# ESP32DevKitCv4_SA8x8_Rearrange.net
KiCad netlist of a schematic drawn in EAGLE
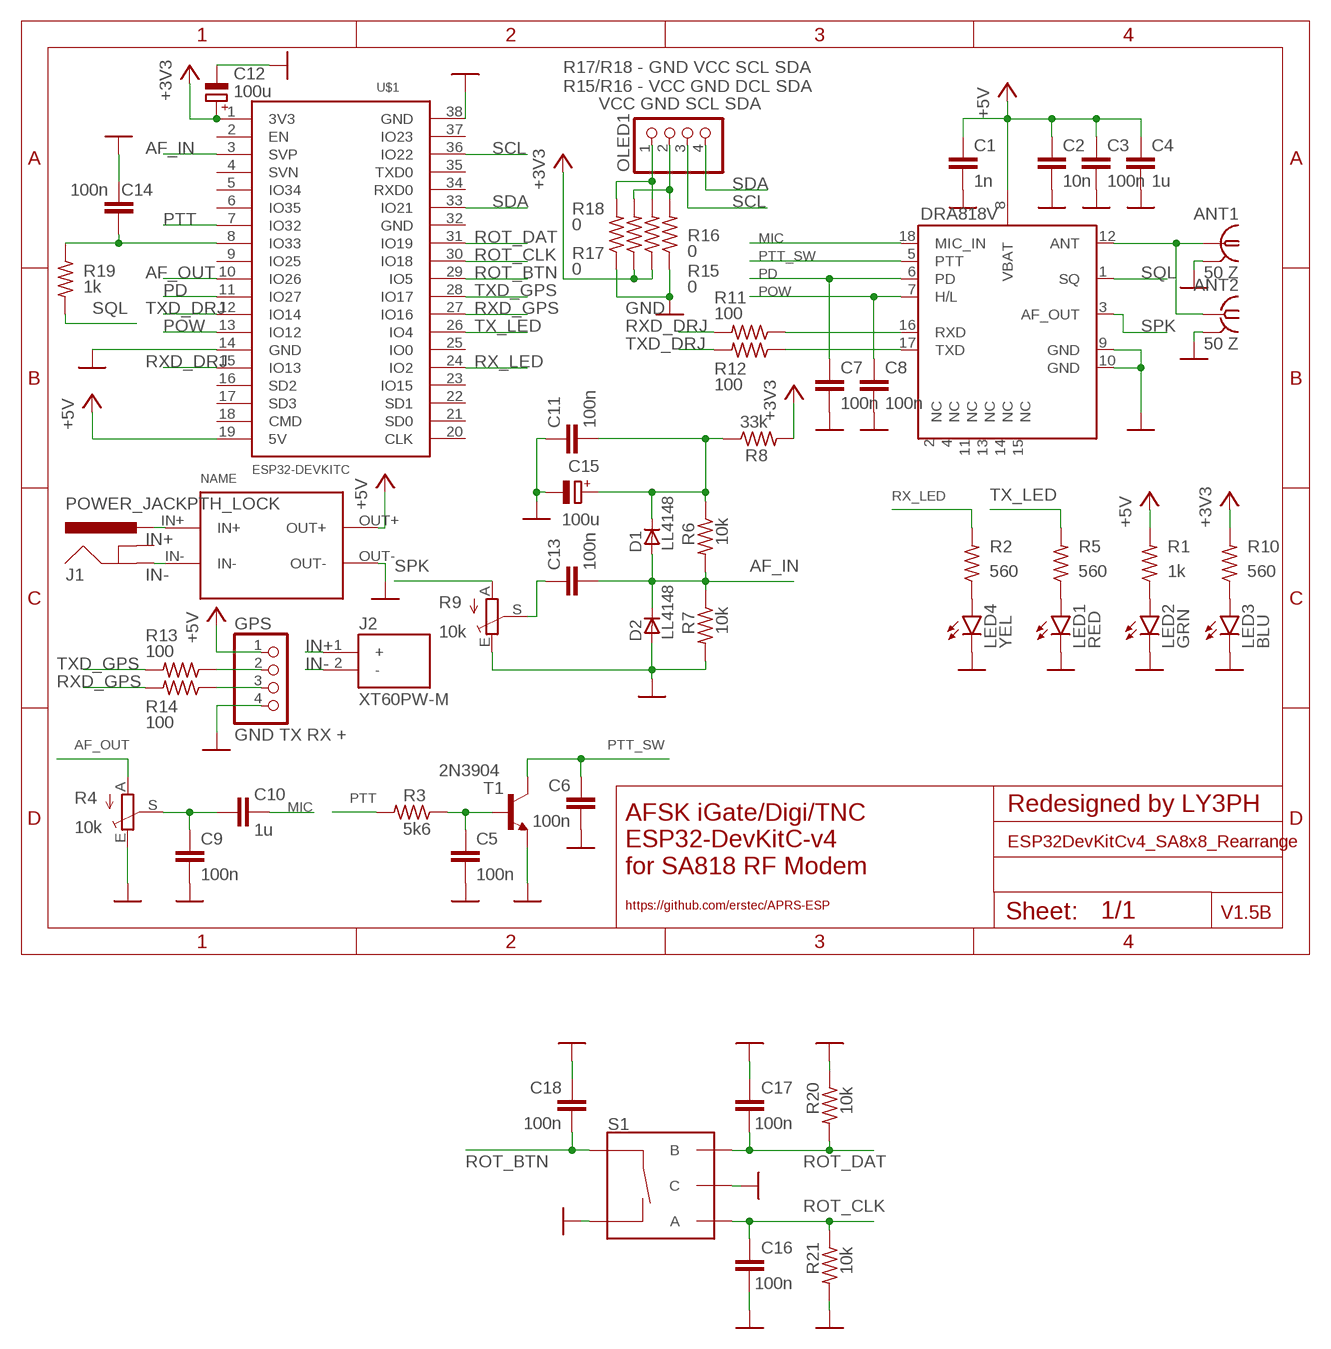
[diagram p0: schematic, sheet 1]

(export (version "E")
  (design (tool "Eeschema 10.0.6"))
  (components
    (comp (ref "ANT1")
      (value "50 Z")
      (footprint "eagle-import:LTI-SASF54GT")
      (libsource (lib "eagle-import") (part "LTI-SASF54GT"))
    )
    (comp (ref "ANT2")
      (value "50 Z")
      (footprint "eagle-import:J502-ND-142-0701-801_806")
      (fields (field (name "MF") "JOHNSON COMPONENTS") (field (name "MPN") "142-0701-801"))
      (libsource (lib "eagle-import") (part "SMA-142-0701-801/806"))
    )
    (comp (ref "C1")
      (value "1n")
      (footprint "eagle-import:C0805")
      (libsource (lib "eagle-import") (part "C-EUC0805"))
    )
    (comp (ref "C2")
      (value "10n")
      (footprint "eagle-import:C0805")
      (libsource (lib "eagle-import") (part "C-EUC0805"))
    )
    (comp (ref "C3")
      (value "100n")
      (footprint "eagle-import:C0805")
      (libsource (lib "eagle-import") (part "C-EUC0805"))
    )
    (comp (ref "C4")
      (value "1u")
      (footprint "eagle-import:C0805")
      (libsource (lib "eagle-import") (part "C-EUC0805"))
    )
    (comp (ref "C5")
      (value "100n")
      (footprint "eagle-import:C0805")
      (libsource (lib "eagle-import") (part "C-EUC0805"))
    )
    (comp (ref "C6")
      (value "100n")
      (footprint "eagle-import:C0805")
      (libsource (lib "eagle-import") (part "C-EUC0805"))
    )
    (comp (ref "C7")
      (value "100n")
      (footprint "eagle-import:C0805")
      (libsource (lib "eagle-import") (part "C-EUC0805"))
    )
    (comp (ref "C8")
      (value "100n")
      (footprint "eagle-import:C0805")
      (libsource (lib "eagle-import") (part "C-EUC0805"))
    )
    (comp (ref "C9")
      (value "100n")
      (footprint "eagle-import:C0805")
      (libsource (lib "eagle-import") (part "C-EUC0805"))
    )
    (comp (ref "C10")
      (value "1u")
      (footprint "eagle-import:C0805")
      (libsource (lib "eagle-import") (part "C-EUC0805"))
    )
    (comp (ref "C11")
      (value "100n")
      (footprint "eagle-import:C0805")
      (libsource (lib "eagle-import") (part "C-EUC0805"))
    )
    (comp (ref "C12")
      (value "100u")
      (footprint "eagle-import:SMC_D")
      (libsource (lib "eagle-import") (part "CPOL-EUSMCD"))
    )
    (comp (ref "C13")
      (value "100n")
      (footprint "eagle-import:C0805")
      (libsource (lib "eagle-import") (part "C-EUC0805"))
    )
    (comp (ref "C14")
      (value "100n")
      (footprint "eagle-import:C0805")
      (libsource (lib "eagle-import") (part "C-EUC0805"))
    )
    (comp (ref "C15")
      (value "100u")
      (footprint "eagle-import:SMC_D")
      (libsource (lib "eagle-import") (part "CPOL-EUSMCD"))
    )
    (comp (ref "C16")
      (value "100n")
      (footprint "eagle-import:C0805")
      (libsource (lib "eagle-import") (part "C-EUC0805"))
    )
    (comp (ref "C17")
      (value "100n")
      (footprint "eagle-import:C0805")
      (libsource (lib "eagle-import") (part "C-EUC0805"))
    )
    (comp (ref "C18")
      (value "100n")
      (footprint "eagle-import:C0805")
      (libsource (lib "eagle-import") (part "C-EUC0805"))
    )
    (comp (ref "D1")
      (value "LL4148")
      (footprint "eagle-import:SOD80_DO213AA_MINIMELF")
      (libsource (lib "eagle-import") (part "LL4148"))
    )
    (comp (ref "D2")
      (value "LL4148")
      (footprint "eagle-import:SOD80_DO213AA_MINIMELF")
      (libsource (lib "eagle-import") (part "LL4148"))
    )
    (comp (ref "DRA818V")
      (value "DRA818A")
      (footprint "eagle-import:DRA818A")
      (libsource (lib "eagle-import") (part "DRA818A"))
    )
    (comp (ref "GPS")
      (value "GND TX RX +")
      (footprint "eagle-import:1X04")
      (libsource (lib "eagle-import") (part "PINHD-1X4"))
    )
    (comp (ref "J1")
      (value "POWER_JACKPTH_LOCK")
      (footprint "eagle-import:POWER_JACK_PTH_LOCK")
      (libsource (lib "eagle-import") (part "POWER_JACKPTH_LOCK"))
    )
    (comp (ref "J2")
      (value "XT60PW-M")
      (footprint "eagle-import:AMASS_XT60PW-M")
      (fields (field (name "MF") "AMASS"))
      (libsource (lib "eagle-import") (part "XT60PW-M"))
    )
    (comp (ref "LED1")
      (value "RED")
      (footprint "eagle-import:CHIP-LED0805")
      (libsource (lib "eagle-import") (part "LEDCHIP-LED0805"))
    )
    (comp (ref "LED2")
      (value "GRN")
      (footprint "eagle-import:CHIP-LED0805")
      (libsource (lib "eagle-import") (part "LEDCHIP-LED0805"))
    )
    (comp (ref "LED3")
      (value "BLU")
      (footprint "eagle-import:CHIP-LED0805")
      (libsource (lib "eagle-import") (part "LEDCHIP-LED0805"))
    )
    (comp (ref "LED4")
      (value "YEL")
      (footprint "eagle-import:CHIP-LED0805")
      (libsource (lib "eagle-import") (part "LEDCHIP-LED0805"))
    )
    (comp (ref "OLED1")
      (value "VCC GND SCL SDA")
      (footprint "eagle-import:1X04")
      (libsource (lib "eagle-import") (part "PINHD-1X4"))
    )
    (comp (ref "R1")
      (value "1k")
      (footprint "eagle-import:R0805")
      (libsource (lib "eagle-import") (part "R-US_R0805"))
    )
    (comp (ref "R2")
      (value "560")
      (footprint "eagle-import:R0805")
      (libsource (lib "eagle-import") (part "R-US_R0805"))
    )
    (comp (ref "R3")
      (value "5k6")
      (footprint "eagle-import:R0805")
      (libsource (lib "eagle-import") (part "R-US_R0805"))
    )
    (comp (ref "R4")
      (value "10k")
      (footprint "eagle-import:CA6H")
      (libsource (lib "eagle-import") (part "TRIM_EU-CA6H"))
    )
    (comp (ref "R5")
      (value "560")
      (footprint "eagle-import:R0805")
      (libsource (lib "eagle-import") (part "R-US_R0805"))
    )
    (comp (ref "R6")
      (value "10k")
      (footprint "eagle-import:R0805")
      (libsource (lib "eagle-import") (part "R-US_R0805"))
    )
    (comp (ref "R7")
      (value "10k")
      (footprint "eagle-import:R0805")
      (libsource (lib "eagle-import") (part "R-US_R0805"))
    )
    (comp (ref "R8")
      (value "33k")
      (footprint "eagle-import:R0805")
      (libsource (lib "eagle-import") (part "R-US_R0805"))
    )
    (comp (ref "R9")
      (value "10k")
      (footprint "eagle-import:CA6H")
      (libsource (lib "eagle-import") (part "TRIM_EU-CA6H"))
    )
    (comp (ref "R10")
      (value "560")
      (footprint "eagle-import:R0805")
      (libsource (lib "eagle-import") (part "R-US_R0805"))
    )
    (comp (ref "R11")
      (value "100")
      (footprint "eagle-import:R0805")
      (libsource (lib "eagle-import") (part "R-US_R0805"))
    )
    (comp (ref "R12")
      (value "100")
      (footprint "eagle-import:R0805")
      (libsource (lib "eagle-import") (part "R-US_R0805"))
    )
    (comp (ref "R13")
      (value "100")
      (footprint "eagle-import:R0805")
      (libsource (lib "eagle-import") (part "R-US_R0805"))
    )
    (comp (ref "R14")
      (value "100")
      (footprint "eagle-import:R0805")
      (libsource (lib "eagle-import") (part "R-US_R0805"))
    )
    (comp (ref "R15")
      (value "0")
      (footprint "eagle-import:R0805")
      (libsource (lib "eagle-import") (part "R-US_R0805"))
    )
    (comp (ref "R16")
      (value "0")
      (footprint "eagle-import:R0805")
      (libsource (lib "eagle-import") (part "R-US_R0805"))
    )
    (comp (ref "R17")
      (value "0")
      (footprint "eagle-import:R0805")
      (libsource (lib "eagle-import") (part "R-US_R0805"))
    )
    (comp (ref "R18")
      (value "0")
      (footprint "eagle-import:R0805")
      (libsource (lib "eagle-import") (part "R-US_R0805"))
    )
    (comp (ref "R19")
      (value "1k")
      (footprint "eagle-import:R0805")
      (libsource (lib "eagle-import") (part "R-US_R0805"))
    )
    (comp (ref "R20")
      (value "10k")
      (footprint "eagle-import:R0805")
      (libsource (lib "eagle-import") (part "R-US_R0805"))
    )
    (comp (ref "R21")
      (value "10k")
      (footprint "eagle-import:R0805")
      (libsource (lib "eagle-import") (part "R-US_R0805"))
    )
    (comp (ref "S1")
      (value "ENCODER-SWITCH")
      (footprint "eagle-import:ROTARY_ENC_PLAIN")
      (libsource (lib "eagle-import") (part "ENCODER-SWITCH"))
    )
    (comp (ref "T1")
      (value "2N3904")
      (footprint "eagle-import:SOT23-BEC")
      (libsource (lib "eagle-import") (part "-NPN-SOT23-BECMMBT3904LT1"))
    )
    (comp (ref "U$1")
      (value "ESP32DEVKITC")
      (footprint "eagle-import:ESP32-DEVKITC")
      (libsource (lib "eagle-import") (part "ESP32DEVKITC"))
    )
    (comp (ref "U$2")
      (value "CP8-ADJ")
      (footprint "eagle-import:CP8-ADJ")
      (libsource (lib "eagle-import") (part "CP8-ADJ"))
    )
  )
  (nets
    (net (code "1") (name "+3V3") (class "Default")
      (node (ref "C12") (pin "+") (pinfunction "+_+") (pintype "passive"))
      (node (ref "R10") (pin "2") (pinfunction "2_2") (pintype "passive"))
      (node (ref "R15") (pin "1") (pinfunction "1_1") (pintype "passive"))
      (node (ref "R17") (pin "1") (pinfunction "1_1") (pintype "passive"))
      (node (ref "R8") (pin "2") (pinfunction "2_2") (pintype "passive"))
      (node (ref "U$1") (pin "1") (pinfunction "3V3_1") (pintype "bidirectional"))
    )
    (net (code "2") (name "+5V") (class "Default")
      (node (ref "C1") (pin "1") (pinfunction "1_1") (pintype "passive"))
      (node (ref "C2") (pin "1") (pinfunction "1_1") (pintype "passive"))
      (node (ref "C3") (pin "1") (pinfunction "1_1") (pintype "passive"))
      (node (ref "C4") (pin "1") (pinfunction "1_1") (pintype "passive"))
      (node (ref "DRA818V") (pin "8") (pinfunction "VBAT_8") (pintype "bidirectional"))
      (node (ref "GPS") (pin "1") (pinfunction "1_1") (pintype "passive"))
      (node (ref "R1") (pin "2") (pinfunction "2_2") (pintype "passive"))
      (node (ref "U$1") (pin "19") (pinfunction "5V_19") (pintype "bidirectional"))
      (node (ref "U$2") (pin "OUT+") (pinfunction "OUT+_OUT+") (pintype "passive"))
    )
    (net (code "3") (name "/AF_IN") (class "Default")
      (node (ref "C13") (pin "2") (pinfunction "2_2") (pintype "passive"))
      (node (ref "D1") (pin "A") (pinfunction "A_A") (pintype "passive"))
      (node (ref "D2") (pin "C") (pinfunction "C_C") (pintype "passive"))
      (node (ref "R6") (pin "2") (pinfunction "2_2") (pintype "passive"))
      (node (ref "R7") (pin "1") (pinfunction "1_1") (pintype "passive"))
      (node (ref "U$1") (pin "3") (pinfunction "SVP_3") (pintype "bidirectional"))
    )
    (net (code "4") (name "/AF_OUT") (class "Default")
      (node (ref "R4") (pin "A") (pinfunction "A_A") (pintype "passive"))
      (node (ref "U$1") (pin "10") (pinfunction "IO26_10") (pintype "bidirectional"))
    )
    (net (code "5") (name "/IN+") (class "Default")
      (node (ref "J1") (pin "PWR") (pinfunction "PWR_PWR") (pintype "bidirectional"))
      (node (ref "J2") (pin "1") (pinfunction "+_1") (pintype "passive"))
      (node (ref "U$2") (pin "IN+") (pinfunction "IN+_IN+") (pintype "passive"))
    )
    (net (code "6") (name "/IN-") (class "Default")
      (node (ref "J1") (pin "GND") (pinfunction "GND_GND") (pintype "bidirectional"))
      (node (ref "J2") (pin "2") (pinfunction "-_2") (pintype "passive"))
      (node (ref "U$2") (pin "IN-") (pinfunction "IN-_IN-") (pintype "passive"))
    )
    (net (code "7") (name "/MIC") (class "Default")
      (node (ref "C10") (pin "2") (pinfunction "2_2") (pintype "passive"))
      (node (ref "DRA818V") (pin "18") (pinfunction "MIC_IN_18") (pintype "bidirectional"))
    )
    (net (code "8") (name "/PD") (class "Default")
      (node (ref "C7") (pin "1") (pinfunction "1_1") (pintype "passive"))
      (node (ref "DRA818V") (pin "6") (pinfunction "PD_6") (pintype "bidirectional"))
      (node (ref "U$1") (pin "11") (pinfunction "IO27_11") (pintype "bidirectional"))
    )
    (net (code "9") (name "/POW") (class "Default")
      (node (ref "C8") (pin "1") (pinfunction "1_1") (pintype "passive"))
      (node (ref "DRA818V") (pin "7") (pinfunction "H/L_7") (pintype "bidirectional"))
      (node (ref "U$1") (pin "13") (pinfunction "IO12_13") (pintype "bidirectional"))
    )
    (net (code "10") (name "/PTT") (class "Default")
      (node (ref "R3") (pin "2") (pinfunction "2_2") (pintype "passive"))
      (node (ref "U$1") (pin "7") (pinfunction "IO32_7") (pintype "bidirectional"))
    )
    (net (code "11") (name "/PTT_SW") (class "Default")
      (node (ref "C6") (pin "1") (pinfunction "1_1") (pintype "passive"))
      (node (ref "DRA818V") (pin "5") (pinfunction "PTT_5") (pintype "bidirectional"))
      (node (ref "T1") (pin "C") (pinfunction "C_C") (pintype "passive"))
    )
    (net (code "12") (name "/ROT_BTN") (class "Default")
      (node (ref "C18") (pin "2") (pinfunction "2_2") (pintype "passive"))
      (node (ref "S1") (pin "SW+") (pinfunction "SW+_SW+") (pintype "bidirectional"))
      (node (ref "U$1") (pin "29") (pinfunction "IO5_29") (pintype "bidirectional"))
    )
    (net (code "13") (name "/ROT_CLK") (class "Default")
      (node (ref "C16") (pin "1") (pinfunction "1_1") (pintype "passive"))
      (node (ref "R21") (pin "1") (pinfunction "1_1") (pintype "passive"))
      (node (ref "S1") (pin "A") (pinfunction "A_A") (pintype "bidirectional"))
      (node (ref "U$1") (pin "30") (pinfunction "IO18_30") (pintype "bidirectional"))
    )
    (net (code "14") (name "/ROT_DAT") (class "Default")
      (node (ref "C17") (pin "2") (pinfunction "2_2") (pintype "passive"))
      (node (ref "R20") (pin "2") (pinfunction "2_2") (pintype "passive"))
      (node (ref "S1") (pin "B") (pinfunction "B_B") (pintype "bidirectional"))
      (node (ref "U$1") (pin "31") (pinfunction "IO19_31") (pintype "bidirectional"))
    )
    (net (code "15") (name "/RXD_DRJ") (class "Default")
      (node (ref "R11") (pin "2") (pinfunction "2_2") (pintype "passive"))
      (node (ref "U$1") (pin "15") (pinfunction "IO13_15") (pintype "bidirectional"))
    )
    (net (code "16") (name "/RXD_GPS") (class "Default")
      (node (ref "R14") (pin "2") (pinfunction "2_2") (pintype "passive"))
      (node (ref "U$1") (pin "27") (pinfunction "IO16_27") (pintype "bidirectional"))
    )
    (net (code "17") (name "/RX_LED") (class "Default")
      (node (ref "R2") (pin "2") (pinfunction "2_2") (pintype "passive"))
      (node (ref "U$1") (pin "24") (pinfunction "IO2_24") (pintype "bidirectional"))
    )
    (net (code "18") (name "/SCL") (class "Default")
      (node (ref "OLED1") (pin "3") (pinfunction "3_3") (pintype "passive"))
      (node (ref "U$1") (pin "36") (pinfunction "IO22_36") (pintype "bidirectional"))
    )
    (net (code "19") (name "/SDA") (class "Default")
      (node (ref "OLED1") (pin "4") (pinfunction "4_4") (pintype "passive"))
      (node (ref "U$1") (pin "33") (pinfunction "IO21_33") (pintype "bidirectional"))
    )
    (net (code "20") (name "/SPK") (class "Default")
      (node (ref "DRA818V") (pin "3") (pinfunction "AF_OUT_3") (pintype "bidirectional"))
      (node (ref "R9") (pin "A") (pinfunction "A_A") (pintype "passive"))
    )
    (net (code "21") (name "/SQL") (class "Default")
      (node (ref "DRA818V") (pin "1") (pinfunction "SQ_1") (pintype "bidirectional"))
      (node (ref "R19") (pin "2") (pinfunction "2_2") (pintype "passive"))
    )
    (net (code "22") (name "/TXD_DRJ") (class "Default")
      (node (ref "R12") (pin "2") (pinfunction "2_2") (pintype "passive"))
      (node (ref "U$1") (pin "12") (pinfunction "IO14_12") (pintype "bidirectional"))
    )
    (net (code "23") (name "/TXD_GPS") (class "Default")
      (node (ref "R13") (pin "2") (pinfunction "2_2") (pintype "passive"))
      (node (ref "U$1") (pin "28") (pinfunction "IO17_28") (pintype "bidirectional"))
    )
    (net (code "24") (name "/TX_LED") (class "Default")
      (node (ref "R5") (pin "2") (pinfunction "2_2") (pintype "passive"))
      (node (ref "U$1") (pin "26") (pinfunction "IO4_26") (pintype "bidirectional"))
    )
    (net (code "25") (name "GND") (class "Default")
      (node (ref "ANT1") (pin "2") (pinfunction "2_2") (pintype "passive"))
      (node (ref "ANT1") (pin "3") (pinfunction "2_3") (pintype "passive"))
      (node (ref "ANT1") (pin "4") (pinfunction "2_4") (pintype "passive"))
      (node (ref "ANT1") (pin "5") (pinfunction "2_5") (pintype "passive"))
      (node (ref "ANT2") (pin "G@1") (pinfunction "2_G@1") (pintype "passive"))
      (node (ref "ANT2") (pin "G@2") (pinfunction "2_G@2") (pintype "passive"))
      (node (ref "ANT2") (pin "G@3") (pinfunction "2_G@3") (pintype "passive"))
      (node (ref "ANT2") (pin "G@4") (pinfunction "2_G@4") (pintype "passive"))
      (node (ref "C1") (pin "2") (pinfunction "2_2") (pintype "passive"))
      (node (ref "C11") (pin "1") (pinfunction "1_1") (pintype "passive"))
      (node (ref "C12") (pin "-") (pinfunction "-_-") (pintype "passive"))
      (node (ref "C14") (pin "2") (pinfunction "2_2") (pintype "passive"))
      (node (ref "C15") (pin "-") (pinfunction "-_-") (pintype "passive"))
      (node (ref "C16") (pin "2") (pinfunction "2_2") (pintype "passive"))
      (node (ref "C17") (pin "1") (pinfunction "1_1") (pintype "passive"))
      (node (ref "C18") (pin "1") (pinfunction "1_1") (pintype "passive"))
      (node (ref "C2") (pin "2") (pinfunction "2_2") (pintype "passive"))
      (node (ref "C3") (pin "2") (pinfunction "2_2") (pintype "passive"))
      (node (ref "C4") (pin "2") (pinfunction "2_2") (pintype "passive"))
      (node (ref "C5") (pin "2") (pinfunction "2_2") (pintype "passive"))
      (node (ref "C6") (pin "2") (pinfunction "2_2") (pintype "passive"))
      (node (ref "C7") (pin "2") (pinfunction "2_2") (pintype "passive"))
      (node (ref "C8") (pin "2") (pinfunction "2_2") (pintype "passive"))
      (node (ref "C9") (pin "2") (pinfunction "2_2") (pintype "passive"))
      (node (ref "D2") (pin "A") (pinfunction "A_A") (pintype "passive"))
      (node (ref "DRA818V") (pin "10") (pinfunction "GND_10") (pintype "bidirectional"))
      (node (ref "DRA818V") (pin "9") (pinfunction "GND_9") (pintype "bidirectional"))
      (node (ref "GPS") (pin "4") (pinfunction "4_4") (pintype "passive"))
      (node (ref "LED1") (pin "C") (pinfunction "C_C") (pintype "passive"))
      (node (ref "LED2") (pin "C") (pinfunction "C_C") (pintype "passive"))
      (node (ref "LED3") (pin "C") (pinfunction "C_C") (pintype "passive"))
      (node (ref "LED4") (pin "C") (pinfunction "C_C") (pintype "passive"))
      (node (ref "R16") (pin "1") (pinfunction "1_1") (pintype "passive"))
      (node (ref "R18") (pin "1") (pinfunction "1_1") (pintype "passive"))
      (node (ref "R20") (pin "1") (pinfunction "1_1") (pintype "passive"))
      (node (ref "R21") (pin "2") (pinfunction "2_2") (pintype "passive"))
      (node (ref "R4") (pin "E") (pinfunction "E_E") (pintype "passive"))
      (node (ref "R7") (pin "2") (pinfunction "2_2") (pintype "passive"))
      (node (ref "R9") (pin "E") (pinfunction "E_E") (pintype "passive"))
      (node (ref "S1") (pin "C") (pinfunction "C_C") (pintype "bidirectional"))
      (node (ref "S1") (pin "SW-") (pinfunction "SW-_SW-") (pintype "bidirectional"))
      (node (ref "T1") (pin "E") (pinfunction "E_E") (pintype "passive"))
      (node (ref "U$1") (pin "14") (pinfunction "GND_14") (pintype "bidirectional"))
      (node (ref "U$1") (pin "38") (pinfunction "GND_38") (pintype "bidirectional"))
      (node (ref "U$2") (pin "OUT-") (pinfunction "OUT-_OUT-") (pintype "passive"))
    )
    (net (code "26") (name "Net-(C5-Pad1)") (class "Default")
      (node (ref "C5") (pin "1") (pinfunction "1_1") (pintype "passive"))
      (node (ref "R3") (pin "1") (pinfunction "1_1") (pintype "passive"))
      (node (ref "T1") (pin "B") (pinfunction "B_B") (pintype "passive"))
    )
    (net (code "27") (name "Net-(C10-Pad1)") (class "Default")
      (node (ref "C10") (pin "1") (pinfunction "1_1") (pintype "passive"))
      (node (ref "C9") (pin "1") (pinfunction "1_1") (pintype "passive"))
      (node (ref "R4") (pin "S") (pinfunction "S_S") (pintype "passive"))
    )
    (net (code "28") (name "Net-(C11-Pad2)") (class "Default")
      (node (ref "C11") (pin "2") (pinfunction "2_2") (pintype "passive"))
      (node (ref "C15") (pin "+") (pinfunction "+_+") (pintype "passive"))
      (node (ref "D1") (pin "C") (pinfunction "C_C") (pintype "passive"))
      (node (ref "R6") (pin "1") (pinfunction "1_1") (pintype "passive"))
      (node (ref "R8") (pin "1") (pinfunction "1_1") (pintype "passive"))
    )
    (net (code "29") (name "Net-(C13-Pad1)") (class "Default")
      (node (ref "C13") (pin "1") (pinfunction "1_1") (pintype "passive"))
      (node (ref "R9") (pin "S") (pinfunction "S_S") (pintype "passive"))
    )
    (net (code "30") (name "Net-(DRA818V-ANT)") (class "Default")
      (node (ref "ANT1") (pin "1") (pinfunction "1_1") (pintype "passive"))
      (node (ref "ANT2") (pin "1") (pinfunction "1_1") (pintype "passive"))
      (node (ref "DRA818V") (pin "12") (pinfunction "ANT_12") (pintype "bidirectional"))
    )
    (net (code "31") (name "Net-(DRA818V-RXD)") (class "Default")
      (node (ref "DRA818V") (pin "16") (pinfunction "RXD_16") (pintype "bidirectional"))
      (node (ref "R11") (pin "1") (pinfunction "1_1") (pintype "passive"))
    )
    (net (code "32") (name "Net-(DRA818V-TXD)") (class "Default")
      (node (ref "DRA818V") (pin "17") (pinfunction "TXD_17") (pintype "bidirectional"))
      (node (ref "R12") (pin "1") (pinfunction "1_1") (pintype "passive"))
    )
    (net (code "33") (name "Net-(GPS-Pad2)") (class "Default")
      (node (ref "GPS") (pin "2") (pinfunction "2_2") (pintype "passive"))
      (node (ref "R13") (pin "1") (pinfunction "1_1") (pintype "passive"))
    )
    (net (code "34") (name "Net-(GPS-Pad3)") (class "Default")
      (node (ref "GPS") (pin "3") (pinfunction "3_3") (pintype "passive"))
      (node (ref "R14") (pin "1") (pinfunction "1_1") (pintype "passive"))
    )
    (net (code "35") (name "Net-(LED1-PadA)") (class "Default")
      (node (ref "LED1") (pin "A") (pinfunction "A_A") (pintype "passive"))
      (node (ref "R5") (pin "1") (pinfunction "1_1") (pintype "passive"))
    )
    (net (code "36") (name "Net-(LED2-PadA)") (class "Default")
      (node (ref "LED2") (pin "A") (pinfunction "A_A") (pintype "passive"))
      (node (ref "R1") (pin "1") (pinfunction "1_1") (pintype "passive"))
    )
    (net (code "37") (name "Net-(LED3-PadA)") (class "Default")
      (node (ref "LED3") (pin "A") (pinfunction "A_A") (pintype "passive"))
      (node (ref "R10") (pin "1") (pinfunction "1_1") (pintype "passive"))
    )
    (net (code "38") (name "Net-(LED4-PadA)") (class "Default")
      (node (ref "LED4") (pin "A") (pinfunction "A_A") (pintype "passive"))
      (node (ref "R2") (pin "1") (pinfunction "1_1") (pintype "passive"))
    )
    (net (code "39") (name "Net-(OLED1-Pad1)") (class "Default")
      (node (ref "OLED1") (pin "1") (pinfunction "1_1") (pintype "passive"))
      (node (ref "R15") (pin "2") (pinfunction "2_2") (pintype "passive"))
      (node (ref "R18") (pin "2") (pinfunction "2_2") (pintype "passive"))
    )
    (net (code "40") (name "Net-(OLED1-Pad2)") (class "Default")
      (node (ref "OLED1") (pin "2") (pinfunction "2_2") (pintype "passive"))
      (node (ref "R16") (pin "2") (pinfunction "2_2") (pintype "passive"))
      (node (ref "R17") (pin "2") (pinfunction "2_2") (pintype "passive"))
    )
    (net (code "41") (name "Net-(U$1-IO33)") (class "Default")
      (node (ref "C14") (pin "1") (pinfunction "1_1") (pintype "passive"))
      (node (ref "R19") (pin "1") (pinfunction "1_1") (pintype "passive"))
      (node (ref "U$1") (pin "8") (pinfunction "IO33_8") (pintype "bidirectional"))
    )
    (net (code "42") (name "unconnected-(DRA818V-NC-Pad2)") (class "Default")
      (node (ref "DRA818V") (pin "2") (pinfunction "NC_2") (pintype "bidirectional"))
    )
    (net (code "43") (name "unconnected-(DRA818V-NC-Pad4)") (class "Default")
      (node (ref "DRA818V") (pin "4") (pinfunction "NC_4") (pintype "bidirectional"))
    )
    (net (code "44") (name "unconnected-(DRA818V-NC-Pad11)") (class "Default")
      (node (ref "DRA818V") (pin "11") (pinfunction "NC_11") (pintype "bidirectional"))
    )
    (net (code "45") (name "unconnected-(DRA818V-NC-Pad13)") (class "Default")
      (node (ref "DRA818V") (pin "13") (pinfunction "NC_13") (pintype "bidirectional"))
    )
    (net (code "46") (name "unconnected-(DRA818V-NC-Pad14)") (class "Default")
      (node (ref "DRA818V") (pin "14") (pinfunction "NC_14") (pintype "bidirectional"))
    )
    (net (code "47") (name "unconnected-(DRA818V-NC-Pad15)") (class "Default")
      (node (ref "DRA818V") (pin "15") (pinfunction "NC_15") (pintype "bidirectional"))
    )
    (net (code "48") (name "unconnected-(J1-PadGNDBREAK)") (class "Default")
      (node (ref "J1") (pin "GNDBREAK") (pinfunction "GNDBREAK_GNDBREAK") (pintype "bidirectional"))
    )
    (net (code "49") (name "unconnected-(U$1-CLK-Pad20)") (class "Default")
      (node (ref "U$1") (pin "20") (pinfunction "CLK_20") (pintype "bidirectional"))
    )
    (net (code "50") (name "unconnected-(U$1-CMD-Pad18)") (class "Default")
      (node (ref "U$1") (pin "18") (pinfunction "CMD_18") (pintype "bidirectional"))
    )
    (net (code "51") (name "unconnected-(U$1-EN-Pad2)") (class "Default")
      (node (ref "U$1") (pin "2") (pinfunction "EN_2") (pintype "bidirectional"))
    )
    (net (code "52") (name "unconnected-(U$1-GND-Pad32)") (class "Default")
      (node (ref "U$1") (pin "32") (pinfunction "GND_32") (pintype "bidirectional"))
    )
    (net (code "53") (name "unconnected-(U$1-IO0-Pad25)") (class "Default")
      (node (ref "U$1") (pin "25") (pinfunction "IO0_25") (pintype "bidirectional"))
    )
    (net (code "54") (name "unconnected-(U$1-IO15-Pad23)") (class "Default")
      (node (ref "U$1") (pin "23") (pinfunction "IO15_23") (pintype "bidirectional"))
    )
    (net (code "55") (name "unconnected-(U$1-IO23-Pad37)") (class "Default")
      (node (ref "U$1") (pin "37") (pinfunction "IO23_37") (pintype "bidirectional"))
    )
    (net (code "56") (name "unconnected-(U$1-IO25-Pad9)") (class "Default")
      (node (ref "U$1") (pin "9") (pinfunction "IO25_9") (pintype "bidirectional"))
    )
    (net (code "57") (name "unconnected-(U$1-IO34-Pad5)") (class "Default")
      (node (ref "U$1") (pin "5") (pinfunction "IO34_5") (pintype "bidirectional"))
    )
    (net (code "58") (name "unconnected-(U$1-IO35-Pad6)") (class "Default")
      (node (ref "U$1") (pin "6") (pinfunction "IO35_6") (pintype "bidirectional"))
    )
    (net (code "59") (name "unconnected-(U$1-RXD0-Pad34)") (class "Default")
      (node (ref "U$1") (pin "34") (pinfunction "RXD0_34") (pintype "bidirectional"))
    )
    (net (code "60") (name "unconnected-(U$1-SD0-Pad21)") (class "Default")
      (node (ref "U$1") (pin "21") (pinfunction "SD0_21") (pintype "bidirectional"))
    )
    (net (code "61") (name "unconnected-(U$1-SD1-Pad22)") (class "Default")
      (node (ref "U$1") (pin "22") (pinfunction "SD1_22") (pintype "bidirectional"))
    )
    (net (code "62") (name "unconnected-(U$1-SD2-Pad16)") (class "Default")
      (node (ref "U$1") (pin "16") (pinfunction "SD2_16") (pintype "bidirectional"))
    )
    (net (code "63") (name "unconnected-(U$1-SD3-Pad17)") (class "Default")
      (node (ref "U$1") (pin "17") (pinfunction "SD3_17") (pintype "bidirectional"))
    )
    (net (code "64") (name "unconnected-(U$1-SVN-Pad4)") (class "Default")
      (node (ref "U$1") (pin "4") (pinfunction "SVN_4") (pintype "bidirectional"))
    )
    (net (code "65") (name "unconnected-(U$1-TXD0-Pad35)") (class "Default")
      (node (ref "U$1") (pin "35") (pinfunction "TXD0_35") (pintype "bidirectional"))
    )
  )
)
